# ADG736-Breakout.net
KiCad netlist of a schematic drawn in EAGLE
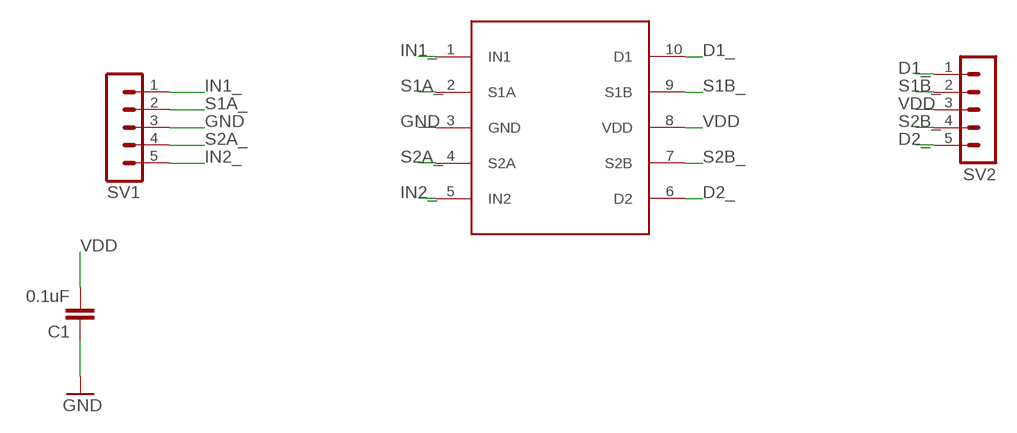
[diagram p0: schematic, sheet 1]

(export (version "E")
  (design (tool "Eeschema 10.0.6"))
  (components
    (comp (ref "C1")
      (value "0.1uF")
      (footprint "eagle-import:C0805")
      (libsource (lib "eagle-import") (part "C-EUC0805"))
    )
    (comp (ref "SV1")
      (value "MA05-1")
      (footprint "eagle-import:MA05-1")
      (libsource (lib "eagle-import") (part "MA05-1"))
    )
    (comp (ref "SV2")
      (value "MA05-1")
      (footprint "eagle-import:MA05-1")
      (libsource (lib "eagle-import") (part "MA05-1"))
    )
    (comp (ref "U$1")
      (value "ADG736")
      (footprint "eagle-import:ADG736")
      (libsource (lib "eagle-import") (part "ADG736"))
    )
  )
  (nets
    (net (code "1") (name "/D1_") (class "Default")
      (node (ref "SV2") (pin "1") (pinfunction "1_1") (pintype "passive"))
      (node (ref "U$1") (pin "10") (pinfunction "D1_10") (pintype "bidirectional"))
    )
    (net (code "2") (name "/D2_") (class "Default")
      (node (ref "SV2") (pin "5") (pinfunction "5_5") (pintype "passive"))
      (node (ref "U$1") (pin "6") (pinfunction "D2_6") (pintype "bidirectional"))
    )
    (net (code "3") (name "/IN1_") (class "Default")
      (node (ref "SV1") (pin "1") (pinfunction "1_1") (pintype "passive"))
      (node (ref "U$1") (pin "1") (pinfunction "IN1_1") (pintype "bidirectional"))
    )
    (net (code "4") (name "/IN2_") (class "Default")
      (node (ref "SV1") (pin "5") (pinfunction "5_5") (pintype "passive"))
      (node (ref "U$1") (pin "5") (pinfunction "IN2_5") (pintype "bidirectional"))
    )
    (net (code "5") (name "/S1A_") (class "Default")
      (node (ref "SV1") (pin "2") (pinfunction "2_2") (pintype "passive"))
      (node (ref "U$1") (pin "2") (pinfunction "S1A_2") (pintype "bidirectional"))
    )
    (net (code "6") (name "/S1B_") (class "Default")
      (node (ref "SV2") (pin "2") (pinfunction "2_2") (pintype "passive"))
      (node (ref "U$1") (pin "9") (pinfunction "S1B_9") (pintype "bidirectional"))
    )
    (net (code "7") (name "/S2A_") (class "Default")
      (node (ref "SV1") (pin "4") (pinfunction "4_4") (pintype "passive"))
      (node (ref "U$1") (pin "4") (pinfunction "S2A_4") (pintype "bidirectional"))
    )
    (net (code "8") (name "/S2B_") (class "Default")
      (node (ref "SV2") (pin "4") (pinfunction "4_4") (pintype "passive"))
      (node (ref "U$1") (pin "7") (pinfunction "S2B_7") (pintype "bidirectional"))
    )
    (net (code "9") (name "/VDD") (class "Default")
      (node (ref "C1") (pin "2") (pinfunction "2_2") (pintype "passive"))
      (node (ref "SV2") (pin "3") (pinfunction "3_3") (pintype "passive"))
      (node (ref "U$1") (pin "8") (pinfunction "VDD_8") (pintype "bidirectional"))
    )
    (net (code "10") (name "GND") (class "Default")
      (node (ref "C1") (pin "1") (pinfunction "1_1") (pintype "passive"))
      (node (ref "SV1") (pin "3") (pinfunction "3_3") (pintype "passive"))
      (node (ref "U$1") (pin "3") (pinfunction "GND_3") (pintype "bidirectional"))
    )
  )
)
